# MiSTer_Direct_Video_to_Comp_Adapter.net
KiCad netlist of a schematic drawn in EAGLE
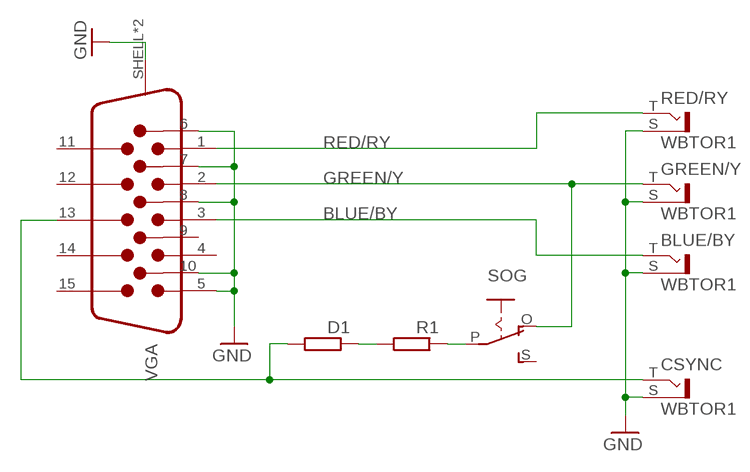
[diagram p0: schematic, sheet 1]

(export (version "E")
  (design (tool "Eeschema 10.0.6"))
  (components
    (comp (ref "BLUE/BY")
      (value "WBTOR1")
      (footprint "eagle-import:WBTOR1")
      (fields (field (name "MPN") "WBTOR 1 BLACK"))
      (libsource (lib "eagle-import") (part "WBTOR1"))
    )
    (comp (ref "CSYNC")
      (value "WBTOR1")
      (footprint "eagle-import:WBTOR1")
      (fields (field (name "MPN") "WBTOR 1 BLACK"))
      (libsource (lib "eagle-import") (part "WBTOR1"))
    )
    (comp (ref "D1")
      (value "R-EU_R1206")
      (footprint "eagle-import:R1206")
      (libsource (lib "eagle-import") (part "R-EU_R1206"))
    )
    (comp (ref "GREEN/Y")
      (value "WBTOR1")
      (footprint "eagle-import:WBTOR1")
      (fields (field (name "MPN") "WBTOR 1 BLACK"))
      (libsource (lib "eagle-import") (part "WBTOR1"))
    )
    (comp (ref "R1")
      (value "R-EU_R0603")
      (footprint "eagle-import:R0603")
      (libsource (lib "eagle-import") (part "R-EU_R0603"))
    )
    (comp (ref "RED/RY")
      (value "WBTOR1")
      (footprint "eagle-import:WBTOR1")
      (fields (field (name "MPN") "WBTOR 1 BLACK"))
      (libsource (lib "eagle-import") (part "WBTOR1"))
    )
    (comp (ref "SOG")
      (value "EG1218S")
      (footprint "eagle-import:EG1218")
      (libsource (lib "eagle-import") (part "EG1218S"))
    )
    (comp (ref "VGA")
      (value "618015331023")
      (footprint "eagle-import:618015331023")
      (libsource (lib "eagle-import") (part "618015331023"))
    )
  )
  (nets
    (net (code "1") (name "/BLUE{slash}BY") (class "Default")
      (node (ref "BLUE/BY") (pin "T") (pinfunction "T_T") (pintype "passive"))
      (node (ref "VGA") (pin "3") (pinfunction "3_3") (pintype "bidirectional"))
    )
    (net (code "2") (name "/GREEN{slash}Y") (class "Default")
      (node (ref "GREEN/Y") (pin "T") (pinfunction "T_T") (pintype "passive"))
      (node (ref "SOG") (pin "O") (pinfunction "O_O") (pintype "passive"))
      (node (ref "VGA") (pin "2") (pinfunction "2_2") (pintype "bidirectional"))
    )
    (net (code "3") (name "/RED{slash}RY") (class "Default")
      (node (ref "RED/RY") (pin "T") (pinfunction "T_T") (pintype "passive"))
      (node (ref "VGA") (pin "1") (pinfunction "1_1") (pintype "bidirectional"))
    )
    (net (code "4") (name "GND") (class "Default")
      (node (ref "BLUE/BY") (pin "S") (pinfunction "S_S") (pintype "passive"))
      (node (ref "CSYNC") (pin "S") (pinfunction "S_S") (pintype "passive"))
      (node (ref "GREEN/Y") (pin "S") (pinfunction "S_S") (pintype "passive"))
      (node (ref "RED/RY") (pin "S") (pinfunction "S_S") (pintype "passive"))
      (node (ref "VGA") (pin "10") (pinfunction "10_10") (pintype "bidirectional"))
      (node (ref "VGA") (pin "5") (pinfunction "5_5") (pintype "bidirectional"))
      (node (ref "VGA") (pin "6") (pinfunction "6_6") (pintype "bidirectional"))
      (node (ref "VGA") (pin "7") (pinfunction "7_7") (pintype "bidirectional"))
      (node (ref "VGA") (pin "8") (pinfunction "8_8") (pintype "bidirectional"))
      (node (ref "VGA") (pin "SHELL") (pinfunction "SHIELD_SHELL") (pintype "bidirectional"))
      (node (ref "VGA") (pin "SHELL1") (pinfunction "SHIELD_SHELL1") (pintype "bidirectional"))
    )
    (net (code "5") (name "Net-(CSYNC-PadT)") (class "Default")
      (node (ref "CSYNC") (pin "T") (pinfunction "T_T") (pintype "passive"))
      (node (ref "D1") (pin "2") (pinfunction "2_2") (pintype "passive"))
      (node (ref "VGA") (pin "13") (pinfunction "13_13") (pintype "bidirectional"))
    )
    (net (code "6") (name "Net-(D1-Pad1)") (class "Default")
      (node (ref "D1") (pin "1") (pinfunction "1_1") (pintype "passive"))
      (node (ref "R1") (pin "2") (pinfunction "2_2") (pintype "passive"))
    )
    (net (code "7") (name "Net-(R1-Pad1)") (class "Default")
      (node (ref "R1") (pin "1") (pinfunction "1_1") (pintype "passive"))
      (node (ref "SOG") (pin "P") (pinfunction "P_P") (pintype "passive"))
    )
    (net (code "8") (name "unconnected-(SOG-PadS)") (class "Default")
      (node (ref "SOG") (pin "S") (pinfunction "S_S") (pintype "passive"))
    )
    (net (code "9") (name "unconnected-(VGA-Pad4)") (class "Default")
      (node (ref "VGA") (pin "4") (pinfunction "4_4") (pintype "bidirectional"))
    )
    (net (code "10") (name "unconnected-(VGA-Pad9)") (class "Default")
      (node (ref "VGA") (pin "9") (pinfunction "9_9") (pintype "bidirectional"))
    )
    (net (code "11") (name "unconnected-(VGA-Pad11)") (class "Default")
      (node (ref "VGA") (pin "11") (pinfunction "11_11") (pintype "bidirectional"))
    )
    (net (code "12") (name "unconnected-(VGA-Pad12)") (class "Default")
      (node (ref "VGA") (pin "12") (pinfunction "12_12") (pintype "bidirectional"))
    )
    (net (code "13") (name "unconnected-(VGA-Pad14)") (class "Default")
      (node (ref "VGA") (pin "14") (pinfunction "14_14") (pintype "bidirectional"))
    )
    (net (code "14") (name "unconnected-(VGA-Pad15)") (class "Default")
      (node (ref "VGA") (pin "15") (pinfunction "15_15") (pintype "bidirectional"))
    )
  )
)
